# OpenPLCv0_2_0_IOController.net
KiCad netlist of a schematic drawn in Altium Designer
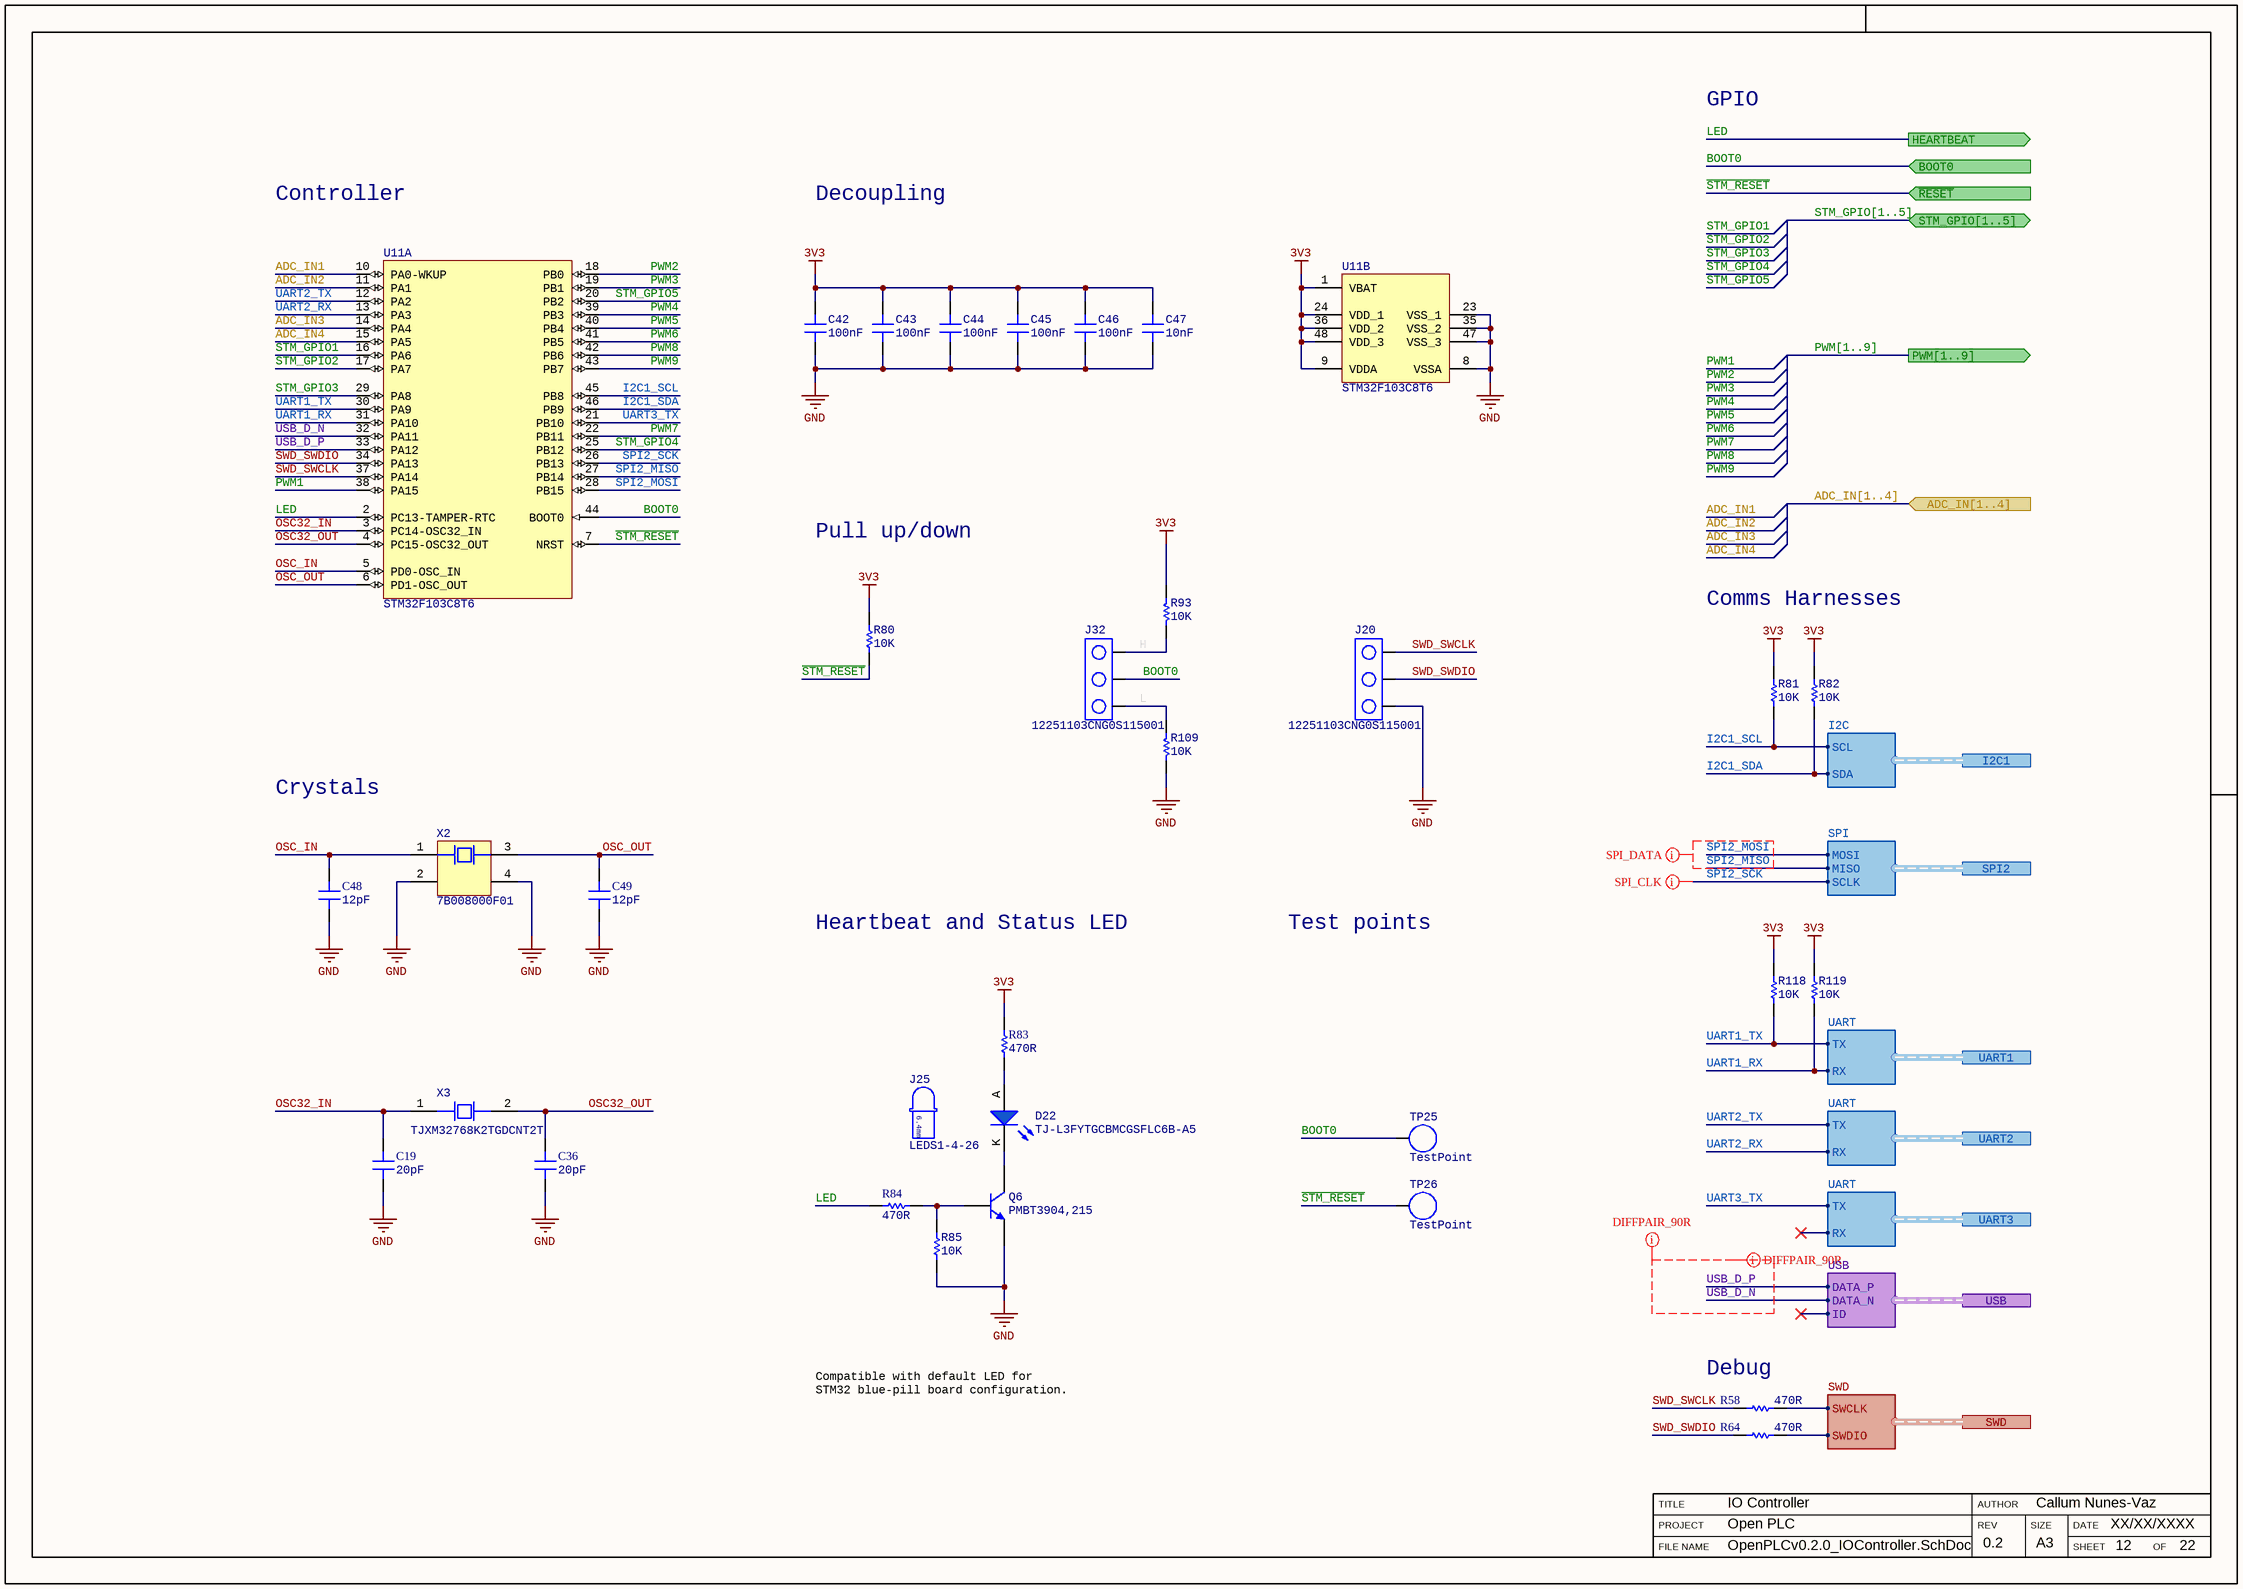
[diagram p0: OpenPLCv0.2.0_IOController.SchDoc]

(export (version "E")
  (design (tool "Eeschema 10.0.6"))
  (components
    (comp (ref "C19")
      (value "CC0402JRNPO9BN200")
      (footprint "SMD_CAP_0402(1005)_N")
      (description "20pF ±5% 50V NP0 0402 Multilayer Ceramic Capacitors MLCC - SMD/SMT RoHS")
      (fields (field (name "TOLERANCE") "5%") (field (name "CAPACITANCE") "20pF"))
      (libsource (lib "OpenPLCv0.2.0_Capacitor") (part "20pF 0402 50V 5%"))
    )
    (comp (ref "C36")
      (value "CC0402JRNPO9BN200")
      (footprint "SMD_CAP_0402(1005)_N")
      (description "20pF ±5% 50V NP0 0402 Multilayer Ceramic Capacitors MLCC - SMD/SMT RoHS")
      (fields (field (name "TOLERANCE") "5%") (field (name "CAPACITANCE") "20pF"))
      (libsource (lib "OpenPLCv0.2.0_Capacitor") (part "20pF 0402 50V 5%"))
    )
    (comp (ref "C42")
      (value "CC0402KRX5R6BB104")
      (footprint "SMD_CAP_0402(1005)_N")
      (description "100nF ±10% 10V X5R 0402 Multilayer Ceramic Capacitors MLCC - SMD/SMT RoHS")
      (fields (field (name "TOLERANCE") "10%") (field (name "CAPACITANCE") "100nF"))
      (libsource (lib "BrauV2_Capacitor") (part "100nF 0402 10V 10%"))
    )
    (comp (ref "C43")
      (value "CC0402KRX5R6BB104")
      (footprint "SMD_CAP_0402(1005)_N")
      (description "100nF ±10% 10V X5R 0402 Multilayer Ceramic Capacitors MLCC - SMD/SMT RoHS")
      (fields (field (name "TOLERANCE") "10%") (field (name "CAPACITANCE") "100nF"))
      (libsource (lib "BrauV2_Capacitor") (part "100nF 0402 10V 10%"))
    )
    (comp (ref "C44")
      (value "CC0402KRX5R6BB104")
      (footprint "SMD_CAP_0402(1005)_N")
      (description "100nF ±10% 10V X5R 0402 Multilayer Ceramic Capacitors MLCC - SMD/SMT RoHS")
      (fields (field (name "TOLERANCE") "10%") (field (name "CAPACITANCE") "100nF"))
      (libsource (lib "BrauV2_Capacitor") (part "100nF 0402 10V 10%"))
    )
    (comp (ref "C45")
      (value "CC0402KRX5R6BB104")
      (footprint "SMD_CAP_0402(1005)_N")
      (description "100nF ±10% 10V X5R 0402 Multilayer Ceramic Capacitors MLCC - SMD/SMT RoHS")
      (fields (field (name "TOLERANCE") "10%") (field (name "CAPACITANCE") "100nF"))
      (libsource (lib "BrauV2_Capacitor") (part "100nF 0402 10V 10%"))
    )
    (comp (ref "C46")
      (value "CC0402KRX5R6BB104")
      (footprint "SMD_CAP_0402(1005)_N")
      (description "100nF ±10% 10V X5R 0402 Multilayer Ceramic Capacitors MLCC - SMD/SMT RoHS")
      (fields (field (name "TOLERANCE") "10%") (field (name "CAPACITANCE") "100nF"))
      (libsource (lib "BrauV2_Capacitor") (part "100nF 0402 10V 10%"))
    )
    (comp (ref "C47")
      (value "CC0402KRX7R9BB103")
      (footprint "SMD_CAP_0402(1005)_N")
      (description "10nF ±10% 50V X7R 0402 Multilayer Ceramic Capacitors MLCC - SMD/SMT RoHS")
      (fields (field (name "TOLERANCE") "10%") (field (name "CAPACITANCE") "10nF"))
      (libsource (lib "BrauV2_Capacitor") (part "10nF 0402 50V 10%"))
    )
    (comp (ref "C48")
      (value "CC0402JRNPO9BN120")
      (footprint "SMD_CAP_0402(1005)_N")
      (description "12pF ±5% 50V NP0 0402 Multilayer Ceramic Capacitors MLCC - SMD/SMT RoHS")
      (fields (field (name "TOLERANCE") "5%") (field (name "CAPACITANCE") "12pF"))
      (libsource (lib "BrauV2_Capacitor") (part "12pF 0402 50V 5%"))
    )
    (comp (ref "C49")
      (value "CC0402JRNPO9BN120")
      (footprint "SMD_CAP_0402(1005)_N")
      (description "12pF ±5% 50V NP0 0402 Multilayer Ceramic Capacitors MLCC - SMD/SMT RoHS")
      (fields (field (name "TOLERANCE") "5%") (field (name "CAPACITANCE") "12pF"))
      (libsource (lib "BrauV2_Capacitor") (part "12pF 0402 50V 5%"))
    )
    (comp (ref "D22")
      (value "TJ-L3FYTGCBMCGSFLC6B-A5")
      (footprint "LED_3MM_SPACED_6.4MM_BLUE")
      (description "LED 3mm Blue 460nm~470nm 2.7V~3.6V Through Hole Light Emitting Diodes (LED) RoHS C330760")
      (libsource (lib "BrauV2_Diode") (part "TJ-L3FYTGCBMCGSFLC6B-A5"))
    )
    (comp (ref "J20")
      (value "12251103CNG0S115001")
      (footprint "Header_3POS")
      (description "Pin Header 3 1 right-angle，180degrees 2.54mm Through Hole,P=2.54mm Pin Header & Female Header RoHS")
      (libsource (lib "BrauV2_Connector") (part "3-way Jumper"))
    )
    (comp (ref "J25")
      (value "LEDS1-4-26")
      (footprint "3MM_LED_SPACER_6.4MM")
      (description "3mm LED spacer 6.4mm height")
      (libsource (lib "BrauV2_Misc") (part "LEDS1-4-26"))
    )
    (comp (ref "J32")
      (value "12251103CNG0S115001")
      (footprint "Header_3POS")
      (description "Pin Header 3 1 right-angle，180degrees 2.54mm Through Hole,P=2.54mm Pin Header & Female Header RoHS")
      (libsource (lib "BrauV2_Connector") (part "3-way Jumper"))
    )
    (comp (ref "Q6")
      (value "PMBT3904,215")
      (footprint "SOT23-3")
      (description "NPN 200mA 40V 250mW SOT-23(SOT-23-3) Transistors (NPN/PNP) RoHS")
      (libsource (lib "BrauV2_Transistor") (part "PMBT3904,215"))
    )
    (comp (ref "R58")
      (value "RC0402FR-07470RL")
      (footprint "SMD_RES_0402(1005)_N")
      (description "470Ω ±1% 1/16W ±100ppm/℃ 0402 Chip Resistor - Surface Mount RoHS")
      (fields (field (name "TOLERANCE") "1%") (field (name "RESISTANCE") "470R"))
      (libsource (lib "OpenPLCv0.2.0_Resistor") (part "470R 0402 1% 1W"))
    )
    (comp (ref "R64")
      (value "RC0402FR-07470RL")
      (footprint "SMD_RES_0402(1005)_N")
      (description "470Ω ±1% 1/16W ±100ppm/℃ 0402 Chip Resistor - Surface Mount RoHS")
      (fields (field (name "TOLERANCE") "1%") (field (name "RESISTANCE") "470R"))
      (libsource (lib "OpenPLCv0.2.0_Resistor") (part "470R 0402 1% 1W"))
    )
    (comp (ref "R80")
      (value "RC0402FR-0710KL")
      (footprint "SMD_RES_0402(1005)_N")
      (description "10kΩ ±1% 1/16W ±100ppm/℃ 0402 Chip Resistor - Surface Mount RoHS")
      (fields (field (name "TOLERANCE") "1%") (field (name "RESISTANCE") "10K"))
      (libsource (lib "BrauV2_Resistor") (part "10K 0402 1% 1/16W"))
    )
    (comp (ref "R81")
      (value "RC0402FR-0710KL")
      (footprint "SMD_RES_0402(1005)_N")
      (description "10kΩ ±1% 1/16W ±100ppm/℃ 0402 Chip Resistor - Surface Mount RoHS")
      (fields (field (name "TOLERANCE") "1%") (field (name "RESISTANCE") "10K"))
      (libsource (lib "BrauV2_Resistor") (part "10K 0402 1% 1/16W"))
    )
    (comp (ref "R82")
      (value "RC0402FR-0710KL")
      (footprint "SMD_RES_0402(1005)_N")
      (description "10kΩ ±1% 1/16W ±100ppm/℃ 0402 Chip Resistor - Surface Mount RoHS")
      (fields (field (name "TOLERANCE") "1%") (field (name "RESISTANCE") "10K"))
      (libsource (lib "BrauV2_Resistor") (part "10K 0402 1% 1/16W"))
    )
    (comp (ref "R83")
      (value "RC0402FR-07470RL")
      (footprint "SMD_RES_0402(1005)_N")
      (description "470Ω ±1% 1/16W ±100ppm/℃ 0402 Chip Resistor - Surface Mount RoHS")
      (fields (field (name "TOLERANCE") "1%") (field (name "RESISTANCE") "470R"))
      (libsource (lib "BrauV2_Resistor") (part "470R 0402 1% 1W"))
    )
    (comp (ref "R84")
      (value "RC0402FR-07470RL")
      (footprint "SMD_RES_0402(1005)_N")
      (description "470Ω ±1% 1/16W ±100ppm/℃ 0402 Chip Resistor - Surface Mount RoHS")
      (fields (field (name "TOLERANCE") "1%") (field (name "RESISTANCE") "470R"))
      (libsource (lib "BrauV2_Resistor") (part "470R 0402 1% 1W"))
    )
    (comp (ref "R85")
      (value "RC0402FR-0710KL")
      (footprint "SMD_RES_0402(1005)_N")
      (description "10kΩ ±1% 1/16W ±100ppm/℃ 0402 Chip Resistor - Surface Mount RoHS")
      (fields (field (name "TOLERANCE") "1%") (field (name "RESISTANCE") "10K"))
      (libsource (lib "BrauV2_Resistor") (part "10K 0402 1% 1/16W"))
    )
    (comp (ref "R93")
      (value "RC0402FR-0710KL")
      (footprint "SMD_RES_0402(1005)_N")
      (description "10kΩ ±1% 1/16W ±100ppm/℃ 0402 Chip Resistor - Surface Mount RoHS")
      (fields (field (name "TOLERANCE") "1%") (field (name "RESISTANCE") "10K"))
      (libsource (lib "BrauV2_Resistor") (part "10K 0402 1% 1/16W"))
    )
    (comp (ref "R109")
      (value "RC0402FR-0710KL")
      (footprint "SMD_RES_0402(1005)_N")
      (description "10kΩ ±1% 1/16W ±100ppm/℃ 0402 Chip Resistor - Surface Mount RoHS")
      (fields (field (name "TOLERANCE") "1%") (field (name "RESISTANCE") "10K"))
      (libsource (lib "BrauV2_Resistor") (part "10K 0402 1% 1/16W"))
    )
    (comp (ref "R118")
      (value "RC0402FR-0710KL")
      (footprint "SMD_RES_0402(1005)_N")
      (description "10kΩ ±1% 1/16W ±100ppm/℃ 0402 Chip Resistor - Surface Mount RoHS")
      (fields (field (name "TOLERANCE") "1%") (field (name "RESISTANCE") "10K"))
      (libsource (lib "BrauV2_Resistor") (part "10K 0402 1% 1/16W"))
    )
    (comp (ref "R119")
      (value "RC0402FR-0710KL")
      (footprint "SMD_RES_0402(1005)_N")
      (description "10kΩ ±1% 1/16W ±100ppm/℃ 0402 Chip Resistor - Surface Mount RoHS")
      (fields (field (name "TOLERANCE") "1%") (field (name "RESISTANCE") "10K"))
      (libsource (lib "BrauV2_Resistor") (part "10K 0402 1% 1/16W"))
    )
    (comp (ref "TP25")
      (value "TestPoint")
      (footprint "Pad")
      (libsource (lib "OpenPLCv0.2.0_Misc") (part "Test point"))
    )
    (comp (ref "TP26")
      (value "TestPoint")
      (footprint "Pad")
      (libsource (lib "OpenPLCv0.2.0_Misc") (part "Test point"))
    )
    (comp (ref "U11")
      (value "STM32F103C8T6")
      (footprint "LQFP32_7x7")
      (libsource (lib "BrauV2_IC") (part "STM32F103C8T6"))
    )
    (comp (ref "X2")
      (value "7B008000F01")
      (footprint "CRYSTAL_3225")
      (description "8MHz ±10ppm 8pF 200Ω SMD-3225_4P SMD Crystal Resonators RoHS")
      (libsource (lib "BrauV2_Misc") (part "7B008000F01"))
    )
    (comp (ref "X3")
      (value "TJXM32768K2TGDCNT2T")
      (footprint "CRYSTAL_2012")
      (description "32.768KHz ±20ppm 12.5pF 70kΩ SMD-2012_2P SMD Crystal Resonators RoHS")
      (libsource (lib "OpenPLCv0.2.0_Misc") (part "TJXM32768K2TGDCNT2T"))
    )
  )
  (nets
    (net (code "6") (name "/ADC_IN1") (class "Default")
      (node (ref "U11") (pin "10") (pinfunction "PA0-WKUP_10") (pintype "bidirectional"))
    )
    (net (code "7") (name "/ADC_IN2") (class "Default")
      (node (ref "U11") (pin "11") (pinfunction "PA1_11") (pintype "bidirectional"))
    )
    (net (code "8") (name "/ADC_IN3") (class "Default")
      (node (ref "U11") (pin "14") (pinfunction "PA4_14") (pintype "bidirectional"))
    )
    (net (code "9") (name "/ADC_IN4") (class "Default")
      (node (ref "U11") (pin "15") (pinfunction "PA5_15") (pintype "bidirectional"))
    )
    (net (code "11") (name "/BOOT0") (class "Default")
      (node (ref "J32") (pin "2") (pinfunction "2_2") (pintype "passive"))
      (node (ref "TP25") (pin "1") (pinfunction "1_1") (pintype "passive"))
      (node (ref "U11") (pin "44") (pinfunction "BOOT0_44") (pintype "input"))
    )
    (net (code "12") (name "/H") (class "Default")
      (node (ref "J32") (pin "1") (pinfunction "1_1") (pintype "passive"))
      (node (ref "R93") (pin "1") (pinfunction "1_1") (pintype "passive"))
    )
    (net (code "13") (name "/I2C1_SCL") (class "Default")
      (node (ref "R81") (pin "1") (pinfunction "1_1") (pintype "passive"))
      (node (ref "U11") (pin "45") (pinfunction "PB8_45") (pintype "bidirectional"))
    )
    (net (code "14") (name "/I2C1_SDA") (class "Default")
      (node (ref "R82") (pin "1") (pinfunction "1_1") (pintype "passive"))
      (node (ref "U11") (pin "46") (pinfunction "PB9_46") (pintype "bidirectional"))
    )
    (net (code "16") (name "/L") (class "Default")
      (node (ref "J32") (pin "3") (pinfunction "3_3") (pintype "passive"))
      (node (ref "R109") (pin "2") (pinfunction "2_2") (pintype "passive"))
    )
    (net (code "17") (name "/LED") (class "Default")
      (node (ref "R84") (pin "2") (pinfunction "2_2") (pintype "passive"))
      (node (ref "U11") (pin "2") (pinfunction "PC13-TAMPER-RTC_2") (pintype "bidirectional"))
    )
    (net (code "18") (name "/OSC32_IN") (class "Default")
      (node (ref "C19") (pin "2") (pinfunction "2_2") (pintype "passive"))
      (node (ref "U11") (pin "3") (pinfunction "PC14-OSC32_IN_3") (pintype "bidirectional"))
      (node (ref "X3") (pin "1") (pinfunction "1_1") (pintype "passive"))
    )
    (net (code "19") (name "/OSC32_OUT") (class "Default")
      (node (ref "C36") (pin "2") (pinfunction "2_2") (pintype "passive"))
      (node (ref "U11") (pin "4") (pinfunction "PC15-OSC32_OUT_4") (pintype "bidirectional"))
      (node (ref "X3") (pin "2") (pinfunction "2_2") (pintype "passive"))
    )
    (net (code "20") (name "/OSC_IN") (class "Default")
      (node (ref "C48") (pin "2") (pinfunction "2_2") (pintype "passive"))
      (node (ref "U11") (pin "5") (pinfunction "PD0-OSC_IN_5") (pintype "bidirectional"))
      (node (ref "X2") (pin "1") (pinfunction "1_1") (pintype "passive"))
    )
    (net (code "21") (name "/OSC_OUT") (class "Default")
      (node (ref "C49") (pin "2") (pinfunction "2_2") (pintype "passive"))
      (node (ref "U11") (pin "6") (pinfunction "PD1-OSC_OUT_6") (pintype "bidirectional"))
      (node (ref "X2") (pin "3") (pinfunction "3_3") (pintype "passive"))
    )
    (net (code "22") (name "/PWM1") (class "Default")
      (node (ref "U11") (pin "38") (pinfunction "PA15_38") (pintype "bidirectional"))
    )
    (net (code "23") (name "/PWM2") (class "Default")
      (node (ref "U11") (pin "18") (pinfunction "PB0_18") (pintype "bidirectional"))
    )
    (net (code "24") (name "/PWM3") (class "Default")
      (node (ref "U11") (pin "19") (pinfunction "PB1_19") (pintype "bidirectional"))
    )
    (net (code "25") (name "/PWM4") (class "Default")
      (node (ref "U11") (pin "39") (pinfunction "PB3_39") (pintype "bidirectional"))
    )
    (net (code "26") (name "/PWM5") (class "Default")
      (node (ref "U11") (pin "40") (pinfunction "PB4_40") (pintype "bidirectional"))
    )
    (net (code "27") (name "/PWM6") (class "Default")
      (node (ref "U11") (pin "41") (pinfunction "PB5_41") (pintype "bidirectional"))
    )
    (net (code "28") (name "/PWM7") (class "Default")
      (node (ref "U11") (pin "22") (pinfunction "PB11_22") (pintype "bidirectional"))
    )
    (net (code "29") (name "/PWM8") (class "Default")
      (node (ref "U11") (pin "42") (pinfunction "PB6_42") (pintype "bidirectional"))
    )
    (net (code "30") (name "/PWM9") (class "Default")
      (node (ref "U11") (pin "43") (pinfunction "PB7_43") (pintype "bidirectional"))
    )
    (net (code "32") (name "/SPI2_MISO") (class "Default")
      (node (ref "U11") (pin "27") (pinfunction "PB14_27") (pintype "bidirectional"))
    )
    (net (code "33") (name "/SPI2_MOSI") (class "Default")
      (node (ref "U11") (pin "28") (pinfunction "PB15_28") (pintype "bidirectional"))
    )
    (net (code "34") (name "/SPI2_SCK") (class "Default")
      (node (ref "U11") (pin "26") (pinfunction "PB13_26") (pintype "bidirectional"))
    )
    (net (code "35") (name "/STM_GPIO1") (class "Default")
      (node (ref "U11") (pin "16") (pinfunction "PA6_16") (pintype "bidirectional"))
    )
    (net (code "36") (name "/STM_GPIO2") (class "Default")
      (node (ref "U11") (pin "17") (pinfunction "PA7_17") (pintype "bidirectional"))
    )
    (net (code "37") (name "/STM_GPIO3") (class "Default")
      (node (ref "U11") (pin "29") (pinfunction "PA8_29") (pintype "bidirectional"))
    )
    (net (code "38") (name "/STM_GPIO4") (class "Default")
      (node (ref "U11") (pin "25") (pinfunction "PB12_25") (pintype "bidirectional"))
    )
    (net (code "39") (name "/STM_GPIO5") (class "Default")
      (node (ref "U11") (pin "20") (pinfunction "PB2_20") (pintype "bidirectional"))
    )
    (net (code "41") (name "/SWCLK") (class "Default")
      (node (ref "R58") (pin "2") (pinfunction "2_2") (pintype "passive"))
    )
    (net (code "42") (name "/SWDIO") (class "Default")
      (node (ref "R64") (pin "2") (pinfunction "2_2") (pintype "passive"))
    )
    (net (code "43") (name "/SWD_SWCLK") (class "Default")
      (node (ref "J20") (pin "1") (pinfunction "1_1") (pintype "passive"))
      (node (ref "R58") (pin "1") (pinfunction "1_1") (pintype "passive"))
      (node (ref "U11") (pin "37") (pinfunction "PA14_37") (pintype "bidirectional"))
    )
    (net (code "44") (name "/SWD_SWDIO") (class "Default")
      (node (ref "J20") (pin "2") (pinfunction "2_2") (pintype "passive"))
      (node (ref "R64") (pin "1") (pinfunction "1_1") (pintype "passive"))
      (node (ref "U11") (pin "34") (pinfunction "PA13_34") (pintype "bidirectional"))
    )
    (net (code "45") (name "/UART1_RX") (class "Default")
      (node (ref "R119") (pin "1") (pinfunction "1_1") (pintype "passive"))
      (node (ref "U11") (pin "31") (pinfunction "PA10_31") (pintype "bidirectional"))
    )
    (net (code "46") (name "/UART1_TX") (class "Default")
      (node (ref "R118") (pin "1") (pinfunction "1_1") (pintype "passive"))
      (node (ref "U11") (pin "30") (pinfunction "PA9_30") (pintype "bidirectional"))
    )
    (net (code "47") (name "/UART2_RX") (class "Default")
      (node (ref "U11") (pin "13") (pinfunction "PA3_13") (pintype "bidirectional"))
    )
    (net (code "48") (name "/UART2_TX") (class "Default")
      (node (ref "U11") (pin "12") (pinfunction "PA2_12") (pintype "bidirectional"))
    )
    (net (code "49") (name "/UART3_TX") (class "Default")
      (node (ref "U11") (pin "21") (pinfunction "PB10_21") (pintype "bidirectional"))
    )
    (net (code "50") (name "/USB_D_N") (class "Default")
      (node (ref "U11") (pin "32") (pinfunction "PA11_32") (pintype "bidirectional"))
    )
    (net (code "51") (name "/USB_D_P") (class "Default")
      (node (ref "U11") (pin "33") (pinfunction "PA12_33") (pintype "bidirectional"))
    )
    (net (code "57") (name "/~{STM_RESET}") (class "Default")
      (node (ref "R80") (pin "1") (pinfunction "1_1") (pintype "passive"))
      (node (ref "TP26") (pin "1") (pinfunction "1_1") (pintype "passive"))
      (node (ref "U11") (pin "7") (pinfunction "NRST_7") (pintype "bidirectional"))
    )
    (net (code "58") (name "3V3") (class "Default")
      (node (ref "C42") (pin "2") (pinfunction "2_2") (pintype "passive"))
      (node (ref "C43") (pin "2") (pinfunction "2_2") (pintype "passive"))
      (node (ref "C44") (pin "2") (pinfunction "2_2") (pintype "passive"))
      (node (ref "C45") (pin "2") (pinfunction "2_2") (pintype "passive"))
      (node (ref "C46") (pin "2") (pinfunction "2_2") (pintype "passive"))
      (node (ref "C47") (pin "2") (pinfunction "2_2") (pintype "passive"))
      (node (ref "R118") (pin "2") (pinfunction "2_2") (pintype "passive"))
      (node (ref "R119") (pin "2") (pinfunction "2_2") (pintype "passive"))
      (node (ref "R80") (pin "2") (pinfunction "2_2") (pintype "passive"))
      (node (ref "R81") (pin "2") (pinfunction "2_2") (pintype "passive"))
      (node (ref "R82") (pin "2") (pinfunction "2_2") (pintype "passive"))
      (node (ref "R83") (pin "1") (pinfunction "1_1") (pintype "passive"))
      (node (ref "R93") (pin "2") (pinfunction "2_2") (pintype "passive"))
      (node (ref "U11") (pin "1") (pinfunction "VBAT_1") (pintype "power_in"))
      (node (ref "U11") (pin "24") (pinfunction "VDD_1_24") (pintype "power_in"))
      (node (ref "U11") (pin "36") (pinfunction "VDD_2_36") (pintype "power_in"))
      (node (ref "U11") (pin "48") (pinfunction "VDD_3_48") (pintype "power_in"))
      (node (ref "U11") (pin "9") (pinfunction "VDDA_9") (pintype "power_in"))
    )
    (net (code "59") (name "GND") (class "Default")
      (node (ref "C19") (pin "1") (pinfunction "1_1") (pintype "passive"))
      (node (ref "C36") (pin "1") (pinfunction "1_1") (pintype "passive"))
      (node (ref "C42") (pin "1") (pinfunction "1_1") (pintype "passive"))
      (node (ref "C43") (pin "1") (pinfunction "1_1") (pintype "passive"))
      (node (ref "C44") (pin "1") (pinfunction "1_1") (pintype "passive"))
      (node (ref "C45") (pin "1") (pinfunction "1_1") (pintype "passive"))
      (node (ref "C46") (pin "1") (pinfunction "1_1") (pintype "passive"))
      (node (ref "C47") (pin "1") (pinfunction "1_1") (pintype "passive"))
      (node (ref "C48") (pin "1") (pinfunction "1_1") (pintype "passive"))
      (node (ref "C49") (pin "1") (pinfunction "1_1") (pintype "passive"))
      (node (ref "J20") (pin "3") (pinfunction "3_3") (pintype "passive"))
      (node (ref "Q6") (pin "2") (pinfunction "E_2") (pintype "passive"))
      (node (ref "R109") (pin "1") (pinfunction "1_1") (pintype "passive"))
      (node (ref "R85") (pin "1") (pinfunction "1_1") (pintype "passive"))
      (node (ref "U11") (pin "23") (pinfunction "VSS_1_23") (pintype "power_in"))
      (node (ref "U11") (pin "35") (pinfunction "VSS_2_35") (pintype "power_in"))
      (node (ref "U11") (pin "47") (pinfunction "VSS_3_47") (pintype "power_in"))
      (node (ref "U11") (pin "8") (pinfunction "VSSA_8") (pintype "power_in"))
      (node (ref "X2") (pin "2") (pinfunction "2_2") (pintype "passive"))
      (node (ref "X2") (pin "4") (pinfunction "4_4") (pintype "passive"))
    )
    (net (code "60") (name "Net-(D22-PadA)") (class "Default")
      (node (ref "D22") (pin "A") (pinfunction "A_A") (pintype "passive"))
      (node (ref "R83") (pin "2") (pinfunction "2_2") (pintype "passive"))
    )
    (net (code "61") (name "Net-(Q6-B)") (class "Default")
      (node (ref "Q6") (pin "1") (pinfunction "B_1") (pintype "passive"))
      (node (ref "R84") (pin "1") (pinfunction "1_1") (pintype "passive"))
      (node (ref "R85") (pin "2") (pinfunction "2_2") (pintype "passive"))
    )
    (net (code "62") (name "Net-(Q6-C)") (class "Default")
      (node (ref "D22") (pin "K") (pinfunction "K_K") (pintype "passive"))
      (node (ref "Q6") (pin "3") (pinfunction "C_3") (pintype "passive"))
    )
  )
)
